# laserControlerArduinoShield.net
KiCad netlist of a schematic drawn in EAGLE
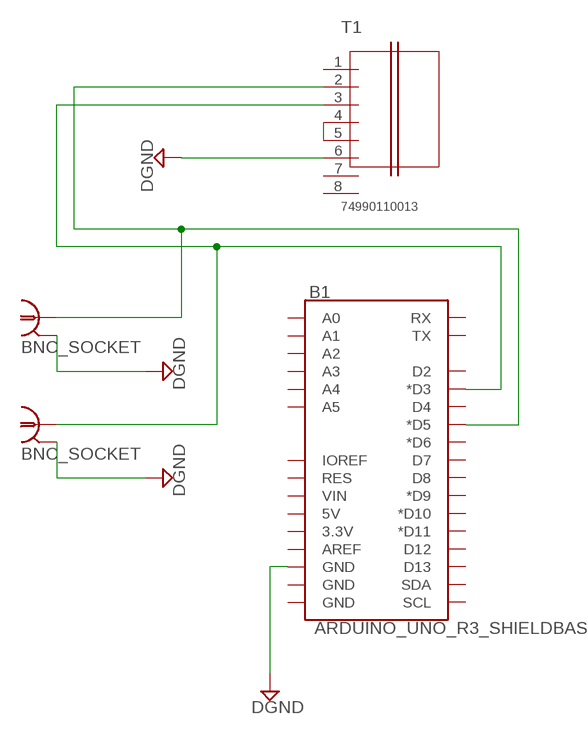
[diagram p0: schematic, sheet 1]

(export (version "E")
  (design (tool "Eeschema 10.0.6"))
  (components
    (comp (ref "B1")
      (value "ARDUINO_UNO_R3_SHIELDBASIC")
      (footprint "eagle-import:UNO_R3_SHIELD")
      (libsource (lib "eagle-import") (part "ARDUINO_UNO_R3_SHIELDBASIC"))
    )
    (comp (ref "BNC_POWER")
      (value "BNC_SOCKET")
      (footprint "eagle-import:BNC_SOCKET")
      (libsource (lib "eagle-import") (part "BNC_SOCKET"))
    )
    (comp (ref "BNC_TTL")
      (value "BNC_SOCKET")
      (footprint "eagle-import:BNC_SOCKET")
      (libsource (lib "eagle-import") (part "BNC_SOCKET"))
    )
    (comp (ref "T1")
      (value "74990110013")
      (footprint "eagle-import:01LAN_RJ45_10_00_STD")
      (libsource (lib "eagle-import") (part "74990110013"))
    )
  )
  (nets
    (net (code "1") (name "DGND") (class "Default")
      (node (ref "B1") (pin "GND@2") (pinfunction "GND_GND@2") (pintype "bidirectional"))
      (node (ref "BNC_POWER") (pin "P$1") (pinfunction "2_P$1") (pintype "passive"))
      (node (ref "BNC_POWER") (pin "P$2") (pinfunction "2_P$2") (pintype "passive"))
      (node (ref "BNC_POWER") (pin "P$3") (pinfunction "2_P$3") (pintype "passive"))
      (node (ref "BNC_POWER") (pin "P$4") (pinfunction "2_P$4") (pintype "passive"))
      (node (ref "BNC_TTL") (pin "P$1") (pinfunction "2_P$1") (pintype "passive"))
      (node (ref "BNC_TTL") (pin "P$2") (pinfunction "2_P$2") (pintype "passive"))
      (node (ref "BNC_TTL") (pin "P$3") (pinfunction "2_P$3") (pintype "passive"))
      (node (ref "BNC_TTL") (pin "P$4") (pinfunction "2_P$4") (pintype "passive"))
      (node (ref "T1") (pin "6") (pinfunction "6_6") (pintype "passive"))
    )
    (net (code "2") (name "Net-(B1-*D3)") (class "Default")
      (node (ref "B1") (pin "D3") (pinfunction "*D3_D3") (pintype "bidirectional"))
      (node (ref "BNC_POWER") (pin "P$SIGNAL") (pinfunction "1_P$SIGNAL") (pintype "passive"))
      (node (ref "T1") (pin "3") (pinfunction "3_3") (pintype "passive"))
    )
    (net (code "3") (name "Net-(B1-*D5)") (class "Default")
      (node (ref "B1") (pin "D5") (pinfunction "*D5_D5") (pintype "bidirectional"))
      (node (ref "BNC_TTL") (pin "P$SIGNAL") (pinfunction "1_P$SIGNAL") (pintype "passive"))
      (node (ref "T1") (pin "2") (pinfunction "2_2") (pintype "passive"))
    )
    (net (code "4") (name "Net-(T1-Pad4)") (class "Default")
      (node (ref "T1") (pin "4") (pinfunction "4_4") (pintype "passive"))
      (node (ref "T1") (pin "5") (pinfunction "5_5") (pintype "passive"))
    )
    (net (code "5") (name "unconnected-(B1-*D6-PadD6)") (class "Default")
      (node (ref "B1") (pin "D6") (pinfunction "*D6_D6") (pintype "bidirectional"))
    )
    (net (code "6") (name "unconnected-(B1-*D9-PadD9)") (class "Default")
      (node (ref "B1") (pin "D9") (pinfunction "*D9_D9") (pintype "bidirectional"))
    )
    (net (code "7") (name "unconnected-(B1-*D10-PadD10)") (class "Default")
      (node (ref "B1") (pin "D10") (pinfunction "*D10_D10") (pintype "bidirectional"))
    )
    (net (code "8") (name "unconnected-(B1-*D11-PadD11)") (class "Default")
      (node (ref "B1") (pin "D11") (pinfunction "*D11_D11") (pintype "bidirectional"))
    )
    (net (code "9") (name "unconnected-(B1-GND-PadGND@0)") (class "Default")
      (node (ref "B1") (pin "GND@0") (pinfunction "GND_GND@0") (pintype "bidirectional"))
    )
    (net (code "10") (name "unconnected-(B1-GND-PadGND@1)") (class "Default")
      (node (ref "B1") (pin "GND@1") (pinfunction "GND_GND@1") (pintype "bidirectional"))
    )
    (net (code "11") (name "unconnected-(B1-Pad3.3V)") (class "Default")
      (node (ref "B1") (pin "3.3V") (pinfunction "3.3V_3.3V") (pintype "bidirectional"))
    )
    (net (code "12") (name "unconnected-(B1-Pad5V)") (class "Default")
      (node (ref "B1") (pin "5V") (pinfunction "5V_5V") (pintype "bidirectional"))
    )
    (net (code "13") (name "unconnected-(B1-PadA0)") (class "Default")
      (node (ref "B1") (pin "A0") (pinfunction "A0_A0") (pintype "bidirectional"))
    )
    (net (code "14") (name "unconnected-(B1-PadA1)") (class "Default")
      (node (ref "B1") (pin "A1") (pinfunction "A1_A1") (pintype "bidirectional"))
    )
    (net (code "15") (name "unconnected-(B1-PadA2)") (class "Default")
      (node (ref "B1") (pin "A2") (pinfunction "A2_A2") (pintype "bidirectional"))
    )
    (net (code "16") (name "unconnected-(B1-PadA3)") (class "Default")
      (node (ref "B1") (pin "A3") (pinfunction "A3_A3") (pintype "bidirectional"))
    )
    (net (code "17") (name "unconnected-(B1-PadA4)") (class "Default")
      (node (ref "B1") (pin "A4") (pinfunction "A4_A4") (pintype "bidirectional"))
    )
    (net (code "18") (name "unconnected-(B1-PadA5)") (class "Default")
      (node (ref "B1") (pin "A5") (pinfunction "A5_A5") (pintype "bidirectional"))
    )
    (net (code "19") (name "unconnected-(B1-PadAREF)") (class "Default")
      (node (ref "B1") (pin "AREF") (pinfunction "AREF_AREF") (pintype "bidirectional"))
    )
    (net (code "20") (name "unconnected-(B1-PadD2)") (class "Default")
      (node (ref "B1") (pin "D2") (pinfunction "D2_D2") (pintype "bidirectional"))
    )
    (net (code "21") (name "unconnected-(B1-PadD4)") (class "Default")
      (node (ref "B1") (pin "D4") (pinfunction "D4_D4") (pintype "bidirectional"))
    )
    (net (code "22") (name "unconnected-(B1-PadD7)") (class "Default")
      (node (ref "B1") (pin "D7") (pinfunction "D7_D7") (pintype "bidirectional"))
    )
    (net (code "23") (name "unconnected-(B1-PadD8)") (class "Default")
      (node (ref "B1") (pin "D8") (pinfunction "D8_D8") (pintype "bidirectional"))
    )
    (net (code "24") (name "unconnected-(B1-PadD12)") (class "Default")
      (node (ref "B1") (pin "D12") (pinfunction "D12_D12") (pintype "bidirectional"))
    )
    (net (code "25") (name "unconnected-(B1-PadD13)") (class "Default")
      (node (ref "B1") (pin "D13") (pinfunction "D13_D13") (pintype "bidirectional"))
    )
    (net (code "26") (name "unconnected-(B1-PadIOREF)") (class "Default")
      (node (ref "B1") (pin "IOREF") (pinfunction "IOREF_IOREF") (pintype "bidirectional"))
    )
    (net (code "27") (name "unconnected-(B1-PadRES)") (class "Default")
      (node (ref "B1") (pin "RES") (pinfunction "RES_RES") (pintype "bidirectional"))
    )
    (net (code "28") (name "unconnected-(B1-PadRX)") (class "Default")
      (node (ref "B1") (pin "RX") (pinfunction "RX_RX") (pintype "bidirectional"))
    )
    (net (code "29") (name "unconnected-(B1-PadSCL)") (class "Default")
      (node (ref "B1") (pin "SCL") (pinfunction "SCL_SCL") (pintype "bidirectional"))
    )
    (net (code "30") (name "unconnected-(B1-PadSDA)") (class "Default")
      (node (ref "B1") (pin "SDA") (pinfunction "SDA_SDA") (pintype "bidirectional"))
    )
    (net (code "31") (name "unconnected-(B1-PadTX)") (class "Default")
      (node (ref "B1") (pin "TX") (pinfunction "TX_TX") (pintype "bidirectional"))
    )
    (net (code "32") (name "unconnected-(B1-PadVIN)") (class "Default")
      (node (ref "B1") (pin "VIN") (pinfunction "VIN_VIN") (pintype "bidirectional"))
    )
    (net (code "33") (name "unconnected-(T1-Pad1)") (class "Default")
      (node (ref "T1") (pin "1") (pinfunction "1_1") (pintype "passive"))
    )
    (net (code "34") (name "unconnected-(T1-Pad7)") (class "Default")
      (node (ref "T1") (pin "7") (pinfunction "7_7") (pintype "passive"))
    )
    (net (code "35") (name "unconnected-(T1-Pad8)") (class "Default")
      (node (ref "T1") (pin "8") (pinfunction "8_8") (pintype "passive"))
    )
  )
)
